# 2230_TubePitotDeporte_Schematic_v1_0_0.net
KiCad netlist of a schematic drawn in Altium Designer
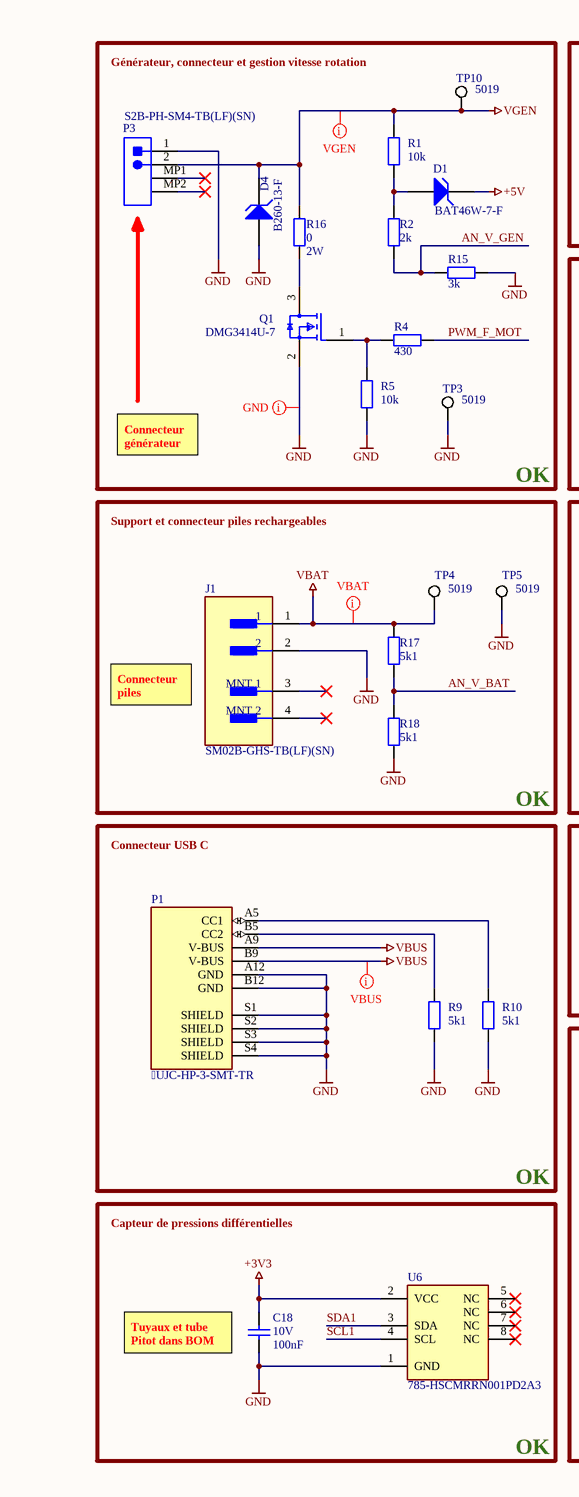
[diagram p0: 2230_TubePitotDeporte_Schematic_v1.0.0.SchDoc, left]
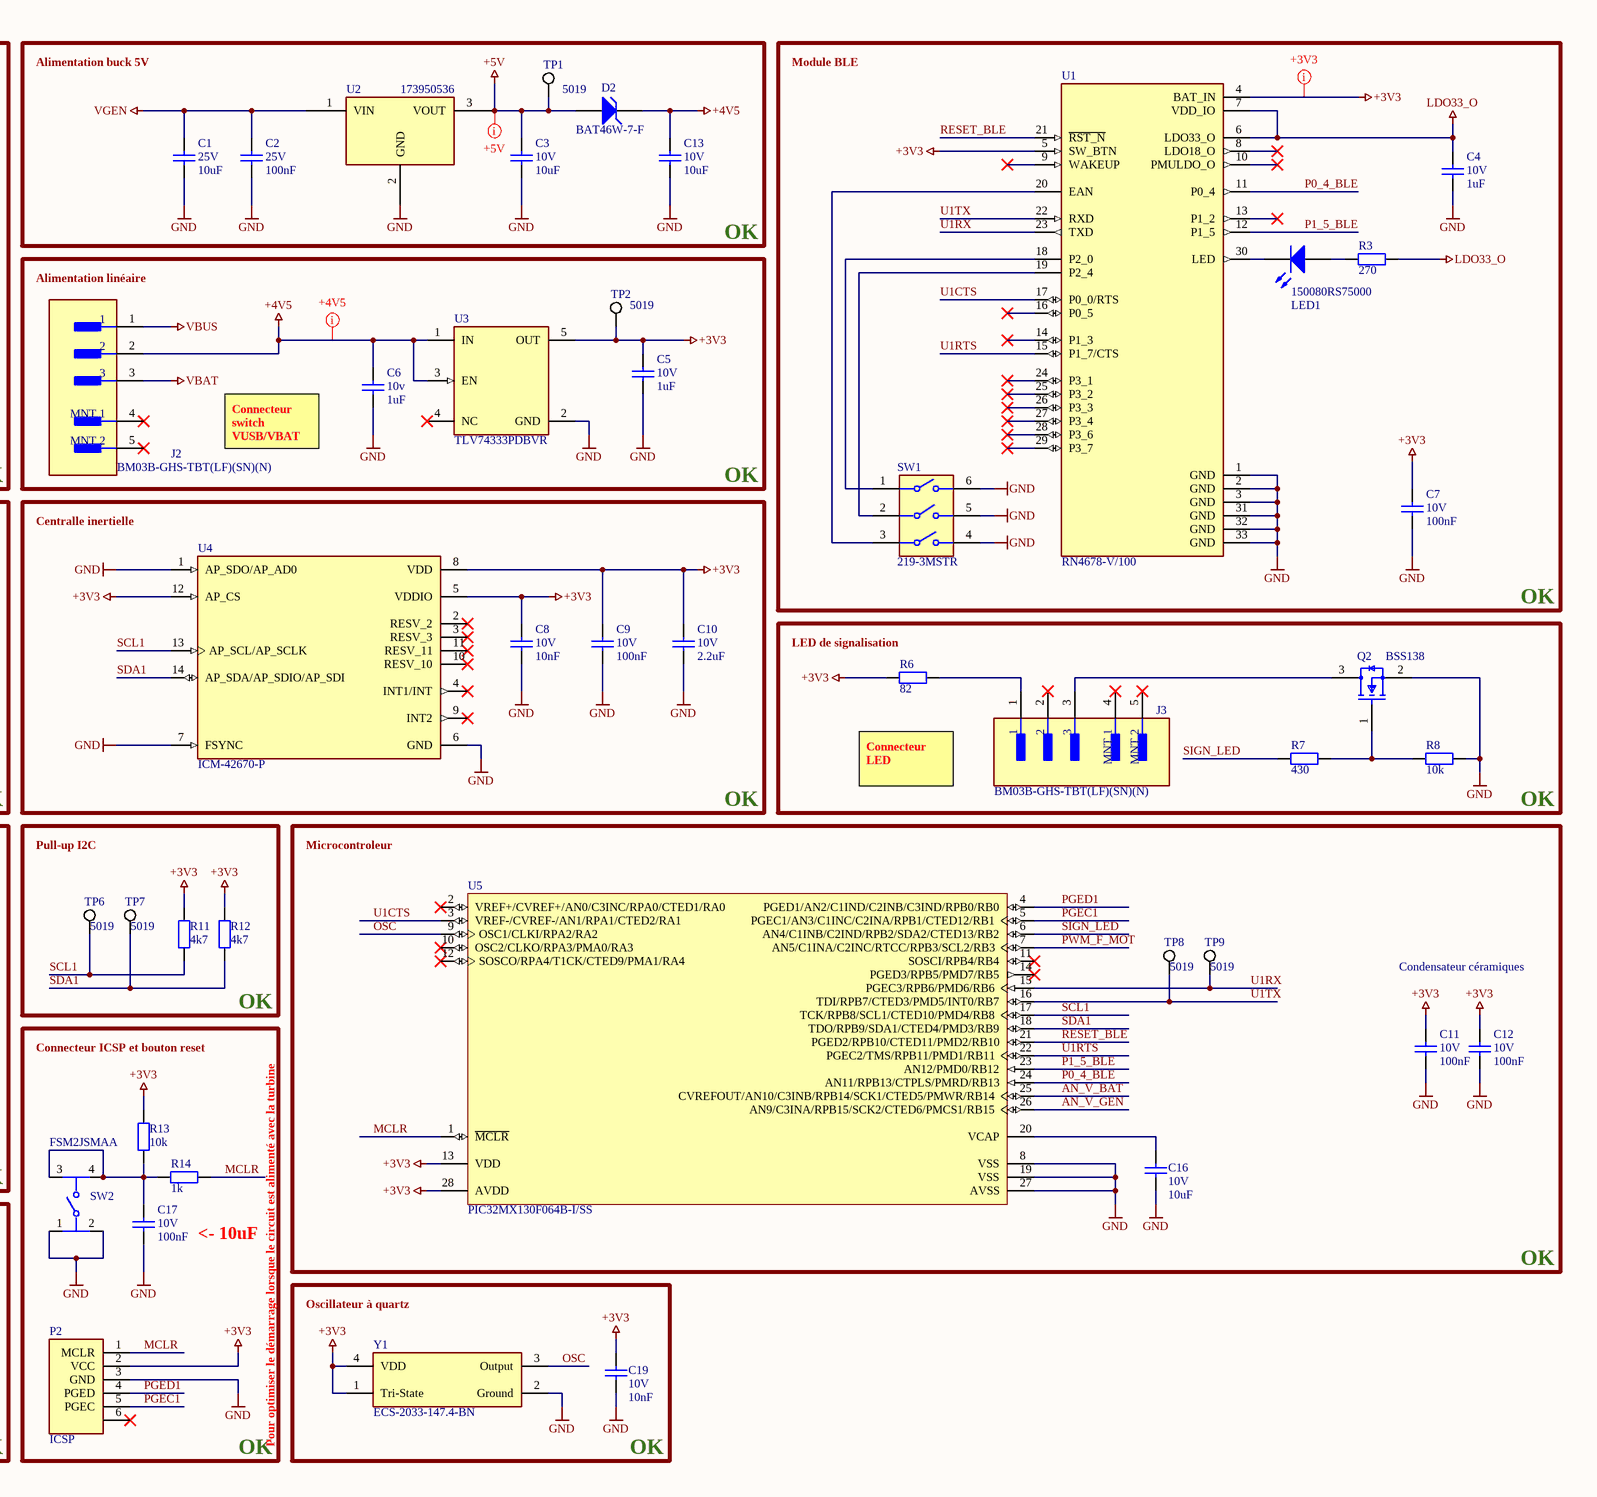
[diagram p1: 2230_TubePitotDeporte_Schematic_v1.0.0.SchDoc, right]

(export (version "E")
  (design (tool "Eeschema 10.0.6"))
  (components
    (comp (ref "C1")
      (value "25V")
      (footprint "0805 CAP T0.95")
      (description "Capacitor")
      (fields (field (name "ALTIUM_VALUE") "10uF") (field (name "PUBLISHER") "Altium Limited"))
      (libsource (lib "Miscellaneous Devices") (part "Cap"))
    )
    (comp (ref "C2")
      (value "25V")
      (footprint "0805 CAP T0.75")
      (description "Capacitor")
      (fields (field (name "ALTIUM_VALUE") "100nF") (field (name "PUBLISHER") "Altium Limited"))
      (libsource (lib "Miscellaneous Devices") (part "Cap"))
    )
    (comp (ref "C3")
      (value "10V")
      (footprint "0805 CAP T0.95")
      (description "Capacitor")
      (fields (field (name "ALTIUM_VALUE") "10uF") (field (name "PUBLISHER") "Altium Limited"))
      (libsource (lib "Miscellaneous Devices") (part "Cap"))
    )
    (comp (ref "C4")
      (value "10V")
      (footprint "0805 CAP T0.75")
      (description "Capacitor")
      (fields (field (name "ALTIUM_VALUE") "1uF") (field (name "PUBLISHER") "Altium Limited"))
      (libsource (lib "Miscellaneous Devices") (part "Cap"))
    )
    (comp (ref "C5")
      (value "10V")
      (footprint "0805 CAP T0.95")
      (description "Capacitor")
      (fields (field (name "ALTIUM_VALUE") "1uF") (field (name "PUBLISHER") "Altium Limited"))
      (libsource (lib "Miscellaneous Devices") (part "Cap"))
    )
    (comp (ref "C6")
      (value "10v")
      (footprint "0805 CAP T0.95")
      (description "Capacitor")
      (fields (field (name "ALTIUM_VALUE") "1uF") (field (name "PUBLISHER") "Altium Limited"))
      (libsource (lib "Miscellaneous Devices") (part "Cap"))
    )
    (comp (ref "C7")
      (value "10V")
      (footprint "0805 CAP T0.75")
      (description "Capacitor")
      (fields (field (name "ALTIUM_VALUE") "100nF") (field (name "PUBLISHER") "Altium Limited"))
      (libsource (lib "Miscellaneous Devices") (part "Cap"))
    )
    (comp (ref "C8")
      (value "10V")
      (footprint "0805 CAP T0.75")
      (description "Capacitor")
      (fields (field (name "ALTIUM_VALUE") "10nF") (field (name "PUBLISHER") "Altium Limited"))
      (libsource (lib "Miscellaneous Devices") (part "Cap"))
    )
    (comp (ref "C9")
      (value "10V")
      (footprint "0805 CAP T0.75")
      (description "Capacitor")
      (fields (field (name "ALTIUM_VALUE") "100nF") (field (name "PUBLISHER") "Altium Limited"))
      (libsource (lib "Miscellaneous Devices") (part "Cap"))
    )
    (comp (ref "C10")
      (value "10V")
      (footprint "0805 CAP T0.75")
      (description "Capacitor")
      (fields (field (name "ALTIUM_VALUE") "2.2uF") (field (name "PUBLISHER") "Altium Limited"))
      (libsource (lib "Miscellaneous Devices") (part "Cap"))
    )
    (comp (ref "C11")
      (value "10V")
      (footprint "0805 CAP T0.75")
      (description "Capacitor")
      (fields (field (name "ALTIUM_VALUE") "100nF") (field (name "PUBLISHER") "Altium Limited"))
      (libsource (lib "Miscellaneous Devices") (part "Cap"))
    )
    (comp (ref "C12")
      (value "10V")
      (footprint "0805 CAP T0.75")
      (description "Capacitor")
      (fields (field (name "ALTIUM_VALUE") "100nF") (field (name "PUBLISHER") "Altium Limited"))
      (libsource (lib "Miscellaneous Devices") (part "Cap"))
    )
    (comp (ref "C13")
      (value "10V")
      (footprint "0805 CAP T0.95")
      (description "Capacitor")
      (fields (field (name "ALTIUM_VALUE") "10uF") (field (name "PUBLISHER") "Altium Limited"))
      (libsource (lib "Miscellaneous Devices") (part "Cap"))
    )
    (comp (ref "C16")
      (value "10V")
      (footprint "0805 CAP T0.95")
      (description "Capacitor")
      (fields (field (name "ALTIUM_VALUE") "10uF") (field (name "PUBLISHER") "Altium Limited"))
      (libsource (lib "Miscellaneous Devices") (part "Cap"))
    )
    (comp (ref "C17")
      (value "10V")
      (footprint "0805 CAP T0.75")
      (description "Capacitor")
      (fields (field (name "ALTIUM_VALUE") "100nF") (field (name "PUBLISHER") "Altium Limited"))
      (libsource (lib "Miscellaneous Devices") (part "Cap"))
    )
    (comp (ref "C18")
      (value "10V")
      (footprint "0805 CAP T0.75")
      (description "Capacitor")
      (fields (field (name "ALTIUM_VALUE") "100nF") (field (name "PUBLISHER") "Altium Limited"))
      (libsource (lib "Miscellaneous Devices") (part "Cap"))
    )
    (comp (ref "C19")
      (value "10V")
      (footprint "0805 CAP T0.75")
      (description "Capacitor")
      (fields (field (name "ALTIUM_VALUE") "10nF") (field (name "PUBLISHER") "Altium Limited"))
      (libsource (lib "Miscellaneous Devices") (part "Cap"))
    )
    (comp (ref "D1")
      (value "BAT46W-7-F")
      (footprint "SOD123")
      (description "Zener Diode")
      (fields (field (name "PUBLISHER") "Altium Limited"))
      (libsource (lib "Miscellaneous Devices") (part "D Zener"))
    )
    (comp (ref "D2")
      (value "BAT46W-7-F")
      (footprint "SOD123")
      (description "Zener Diode")
      (fields (field (name "PUBLISHER") "Altium Limited"))
      (libsource (lib "Miscellaneous Devices") (part "D Zener"))
    )
    (comp (ref "D4")
      (value "B260-13-F")
      (footprint "SMB-2")
      (description "Zener Diode")
      (fields (field (name "PUBLISHER") "Altium Limited"))
      (libsource (lib "Miscellaneous Devices") (part "D Zener"))
    )
    (comp (ref "J1")
      (value "SM02B-GHS-TB(LF)(SN)")
      (footprint "FP-SM02B-GHS-TB_LF_SN-MFG")
      (description "CONN HEADER SMD R/A 2POS 1.25MM")
      (libsource (lib "Altium Content Vault") (part "56ec3178a87b3978bdc1b3682cd516a"))
    )
    (comp (ref "J2")
      (value "BM03B-GHS-TBT(LF)(SN)(N)")
      (footprint "FP-BM03B-GHS-TBT_LF_SN-MFG")
      (description "CONN HEADER SMD 3POS 1.25MM")
      (libsource (lib "") (part "38689d6f3df0f9b234c6ddcef280d85_1"))
    )
    (comp (ref "J3")
      (value "BM03B-GHS-TBT(LF)(SN)(N)")
      (footprint "FP-BM03B-GHS-TBT_LF_SN-MFG")
      (description "CONN HEADER SMD 3POS 1.25MM")
      (libsource (lib "Altium Content Vault") (part "38689d6f3df0f9b234c6ddcef280d85"))
    )
    (comp (ref "LED1")
      (value "150080RS75000")
      (footprint "0805_A")
      (description "SMD mono-color Chip LED, WL-SMCW, Red")
      (fields (field (name "MANUFACTURER") "Wuerth Elektronik"))
      (libsource (lib "Altium Content Vault") (part "WE-LED_K1A2-2"))
    )
    (comp (ref "P1")
      (value "UJC-HP-3-SMT-TR")
      (footprint "UJC-HP-3-SMT-TR")
      (description "USBC connector")
      (libsource (lib "2230_TubePitotDeporte_Library_v1.0.0") (part "UJC-HP-3-SMT-TR"))
    )
    (comp (ref "P2")
      (value "ICSP")
      (footprint "ICSP")
      (description "Prog")
      (libsource (lib "2230_TubePitotDeporte_Library_v1.0.0") (part "ICSP"))
    )
    (comp (ref "P3")
      (value "S2B-PH-SM4-TB(LF)(SN)")
      (footprint "JST- S2B-PH-SM4-TB(LF)(SN)-2_V")
      (description "Male Header, Pitch 2 mm, 1 x 2 Position, Height 5.5 mm, -25 to 85 degC, RoHS, Tape and Reel")
      (libsource (lib "Altium Content Vault") (part "CN-1P-2M-R2"))
    )
    (comp (ref "Q1")
      (value "DMG3414U-7")
      (footprint "FP-SOT23-IPC_B")
      (description "MOSFET N-CH 20V 4.2A SOT23")
      (libsource (lib "Altium Content Vault") (part "381a366367e4312d0f7d2747150cb42"))
    )
    (comp (ref "Q2")
      (value "BSS138")
      (footprint "FP-318-08-IPC_A")
      (description "MOSFET N-CH 50V 220MA SOT-23")
      (libsource (lib "Altium Content Vault") (part "3b9c635fedb024a5347a57b145af9cc"))
    )
    (comp (ref "R1")
      (value "10k")
      (footprint "0805 Res")
      (description "Resistor")
      (fields (field (name "PUBLISHER") "Altium Limited"))
      (libsource (lib "") (part "Res2_1"))
    )
    (comp (ref "R2")
      (value "2k")
      (footprint "0805 Res")
      (description "Resistor")
      (fields (field (name "PUBLISHER") "Altium Limited"))
      (libsource (lib "Miscellaneous Devices") (part "Res2"))
    )
    (comp (ref "R3")
      (value "270")
      (footprint "0805 Res")
      (description "Resistor")
      (fields (field (name "Comment") "270R") (field (name "PUBLISHER") "Altium Limited"))
      (libsource (lib "") (part "Res2_2"))
    )
    (comp (ref "R4")
      (value "430")
      (footprint "0805 Res")
      (description "Resistor")
      (fields (field (name "Comment") "430R") (field (name "PUBLISHER") "Altium Limited"))
      (libsource (lib "") (part "Res2_2"))
    )
    (comp (ref "R5")
      (value "10k")
      (footprint "0805 Res")
      (description "Resistor")
      (fields (field (name "PUBLISHER") "Altium Limited"))
      (libsource (lib "") (part "Res2_1"))
    )
    (comp (ref "R6")
      (value "82")
      (footprint "0805 Res")
      (description "Resistor")
      (fields (field (name "Comment") "82R") (field (name "PUBLISHER") "Altium Limited"))
      (libsource (lib "") (part "Res2_3"))
    )
    (comp (ref "R7")
      (value "430")
      (footprint "0805 Res")
      (description "Resistor")
      (fields (field (name "Comment") "430R") (field (name "PUBLISHER") "Altium Limited"))
      (libsource (lib "") (part "Res2_3"))
    )
    (comp (ref "R8")
      (value "10k")
      (footprint "0805 Res")
      (description "Resistor")
      (fields (field (name "PUBLISHER") "Altium Limited"))
      (libsource (lib "") (part "Res2_3"))
    )
    (comp (ref "R9")
      (value "5k1")
      (footprint "0805 Res")
      (description "Resistor")
      (fields (field (name "PUBLISHER") "Altium Limited"))
      (libsource (lib "") (part "Res2_1"))
    )
    (comp (ref "R10")
      (value "5k1")
      (footprint "0805 Res")
      (description "Resistor")
      (fields (field (name "PUBLISHER") "Altium Limited"))
      (libsource (lib "") (part "Res2_1"))
    )
    (comp (ref "R11")
      (value "4k7")
      (footprint "0805 Res")
      (description "Resistor")
      (fields (field (name "Comment") "10k") (field (name "PUBLISHER") "Altium Limited"))
      (libsource (lib "Miscellaneous Devices") (part "Res2"))
    )
    (comp (ref "R12")
      (value "4k7")
      (footprint "0805 Res")
      (description "Resistor")
      (fields (field (name "Comment") "10k") (field (name "PUBLISHER") "Altium Limited"))
      (libsource (lib "Miscellaneous Devices") (part "Res2"))
    )
    (comp (ref "R13")
      (value "10k")
      (footprint "0805 Res")
      (description "Resistor")
      (fields (field (name "PUBLISHER") "Altium Limited"))
      (libsource (lib "Miscellaneous Devices") (part "Res2"))
    )
    (comp (ref "R14")
      (value "1k")
      (footprint "0805 Res")
      (description "Resistor")
      (fields (field (name "PUBLISHER") "Altium Limited"))
      (libsource (lib "") (part "Res2_2"))
    )
    (comp (ref "R15")
      (value "3k")
      (footprint "0805 Res")
      (description "Resistor")
      (fields (field (name "PUBLISHER") "Altium Limited"))
      (libsource (lib "") (part "Res2_2"))
    )
    (comp (ref "R16")
      (value "0")
      (footprint "RES 2W")
      (description "Resistor")
      (fields
        (field (name "POWER") "2W")
        (field (name "Comment") "0R")
        (field (name "PUBLISHER") "Altium Limited")
      )
      (libsource (lib "") (part "Res2_1"))
    )
    (comp (ref "R17")
      (value "5k1")
      (footprint "0805 Res")
      (description "Resistor")
      (fields (field (name "PUBLISHER") "Altium Limited"))
      (libsource (lib "Miscellaneous Devices") (part "Res2"))
    )
    (comp (ref "R18")
      (value "5k1")
      (footprint "0805 Res")
      (description "Resistor")
      (fields (field (name "PUBLISHER") "Altium Limited"))
      (libsource (lib "Miscellaneous Devices") (part "Res2"))
    )
    (comp (ref "SW1")
      (value "219-3MSTR")
      (footprint "FP-219-3MSTR-MFG")
      (description "SWITCH SLIDE DIP SPST 100MA 20V")
      (libsource (lib "Altium Content Vault") (part "7c490946f25aa2bb1cd4cef5bc3ec4e"))
    )
    (comp (ref "SW2")
      (value "FSM2JSMAA")
      (footprint "FP-FSM2JSMAA-MFG")
      (description "SWITCH TACTILE SPST-NO 0.05A 24V")
      (fields
        (field (name "MANUFACTURER") "TE Connectivity")
        (field (name "OCTOPART") "https://octopart.com/fsm2jsmaa-te+connectivity-41720620")
      )
      (libsource (lib "Altium Content Vault") (part "b8895f3f4cefb76e1819d2863dba89b"))
    )
    (comp (ref "TP1")
      (value "5019")
      (footprint "KSTN-5019_V")
      (description "Test Point, 1 Position SMD, RoHS, Tape and Reel")
      (libsource (lib "Altium Content Vault") (part "TESTPOINT_WHITE"))
    )
    (comp (ref "TP2")
      (value "5019")
      (footprint "KSTN-5019_V")
      (description "Test Point, 1 Position SMD, RoHS, Tape and Reel")
      (libsource (lib "Altium Content Vault") (part "TESTPOINT_WHITE"))
    )
    (comp (ref "TP3")
      (value "5019")
      (footprint "KSTN-5019_V")
      (description "Test Point, 1 Position SMD, RoHS, Tape and Reel")
      (libsource (lib "Altium Content Vault") (part "TESTPOINT_WHITE"))
    )
    (comp (ref "TP4")
      (value "5019")
      (footprint "KSTN-5019_V")
      (description "Test Point, 1 Position SMD, RoHS, Tape and Reel")
      (libsource (lib "Altium Content Vault") (part "TESTPOINT_WHITE"))
    )
    (comp (ref "TP5")
      (value "5019")
      (footprint "KSTN-5019_V")
      (description "Test Point, 1 Position SMD, RoHS, Tape and Reel")
      (libsource (lib "Altium Content Vault") (part "TESTPOINT_WHITE"))
    )
    (comp (ref "TP6")
      (value "5019")
      (footprint "KSTN-5019_V")
      (description "Test Point, 1 Position SMD, RoHS, Tape and Reel")
      (libsource (lib "Altium Content Vault") (part "TESTPOINT_WHITE"))
    )
    (comp (ref "TP7")
      (value "5019")
      (footprint "KSTN-5019_V")
      (description "Test Point, 1 Position SMD, RoHS, Tape and Reel")
      (libsource (lib "Altium Content Vault") (part "TESTPOINT_WHITE"))
    )
    (comp (ref "TP8")
      (value "5019")
      (footprint "KSTN-5019_V")
      (description "Test Point, 1 Position SMD, RoHS, Tape and Reel")
      (libsource (lib "Altium Content Vault") (part "TESTPOINT_WHITE"))
    )
    (comp (ref "TP9")
      (value "5019")
      (footprint "KSTN-5019_V")
      (description "Test Point, 1 Position SMD, RoHS, Tape and Reel")
      (libsource (lib "Altium Content Vault") (part "TESTPOINT_WHITE"))
    )
    (comp (ref "TP10")
      (value "5019")
      (footprint "KSTN-5019_V")
      (description "Test Point, 1 Position SMD, RoHS, Tape and Reel")
      (libsource (lib "Altium Content Vault") (part "TESTPOINT_WHITE"))
    )
    (comp (ref "U1")
      (value "RN4678-V/100")
      (footprint "RN4678-V_RM100")
      (description "Bluetooth Bluetooth v5.0 Transceiver Module 2.4GHz Integrated, Chip Surface Mount")
      (libsource (lib "2230_TubePitotDeporte_Library_v1.0.0") (part "RN4678-V/100"))
    )
    (comp (ref "U2")
      (value "173950536")
      (footprint "173950536")
      (description "Buck 5V")
      (libsource (lib "2230_TubePitotDeporte_Library_v1.0.0") (part "710-173950536"))
    )
    (comp (ref "U3")
      (value "TLV74333PDBVR")
      (footprint "FP-DBV0005A-MFG")
      (description "IC REG LINEAR 3.3V 300MA SOT23-5")
      (fields
        (field (name "OCTOPART") "https://octopart.com/tlv74333pdbvr-texas+instruments-84791760")
        (field (name "MANUFACTURER") "Texas Instruments")
      )
      (libsource (lib "Altium Content Vault") (part "3a8dd6e68b3b0d4ea301bae8a2f3989"))
    )
    (comp (ref "U4")
      (value "ICM-42670-P")
      (footprint "ICM-42670-P")
      (description "6 axis IMU")
      (libsource (lib "2230_TubePitotDeporte_Library_v1.0.0") (part "ICM-42670-P"))
    )
    (comp (ref "U5")
      (value "PIC32MX130F064B-I/SS")
      (footprint "PIC32MX130F064B-I/SS")
      (libsource (lib "2230_TubePitotDeporte_Library_v1.0.0") (part "PIC32MX130F064B-I/SS"))
    )
    (comp (ref "U6")
      (value "785-HSCMRRN001PD2A3")
      (footprint "HSCMRRN001PD2A3")
      (description "Air sensor")
      (libsource (lib "2230_TubePitotDeporte_Library_v1.0.0") (part "785-HSCMRRN001PD2A3"))
    )
    (comp (ref "Y1")
      (value "ECS-2033-147.4-BN")
      (footprint "ECS-2033-147.4-BN")
      (description "ECS-2033-147.4-BN 14.7456 MHz Oscillator")
      (libsource (lib "2230_TubePitotDeporte_Library_v1.0.0") (part "ECS-2033-147.4-BN"))
    )
  )
  (nets
    (net (code "1") (name "+3V3") (class "Default")
      (node (ref "C10") (pin "2") (pinfunction "2_2") (pintype "passive"))
      (node (ref "C11") (pin "2") (pinfunction "2_2") (pintype "passive"))
      (node (ref "C12") (pin "2") (pinfunction "2_2") (pintype "passive"))
      (node (ref "C18") (pin "2") (pinfunction "2_2") (pintype "passive"))
      (node (ref "C19") (pin "1") (pinfunction "1_1") (pintype "passive"))
      (node (ref "C5") (pin "2") (pinfunction "2_2") (pintype "passive"))
      (node (ref "C7") (pin "2") (pinfunction "2_2") (pintype "passive"))
      (node (ref "C8") (pin "2") (pinfunction "2_2") (pintype "passive"))
      (node (ref "C9") (pin "2") (pinfunction "2_2") (pintype "passive"))
      (node (ref "P2") (pin "2") (pinfunction "VCC_2") (pintype "passive"))
      (node (ref "R11") (pin "1") (pinfunction "1_1") (pintype "passive"))
      (node (ref "R12") (pin "1") (pinfunction "1_1") (pintype "passive"))
      (node (ref "R13") (pin "1") (pinfunction "1_1") (pintype "passive"))
      (node (ref "R6") (pin "1") (pinfunction "1_1") (pintype "passive"))
      (node (ref "TP2") (pin "1") (pinfunction "1_1") (pintype "passive"))
      (node (ref "U1") (pin "4") (pinfunction "BAT_IN_4") (pintype "power_in"))
      (node (ref "U1") (pin "5") (pinfunction "SW_BTN_5") (pintype "input"))
      (node (ref "U3") (pin "5") (pinfunction "OUT_5") (pintype "power_in"))
      (node (ref "U4") (pin "12") (pinfunction "AP_CS_12") (pintype "input"))
      (node (ref "U4") (pin "5") (pinfunction "VDDIO_5") (pintype "power_in"))
      (node (ref "U4") (pin "8") (pinfunction "VDD_8") (pintype "power_in"))
      (node (ref "U5") (pin "13") (pinfunction "VDD_13") (pintype "power_in"))
      (node (ref "U5") (pin "28") (pinfunction "AVDD_28") (pintype "power_in"))
      (node (ref "U6") (pin "2") (pinfunction "VCC_2") (pintype "passive"))
      (node (ref "Y1") (pin "1") (pinfunction "Tri-State_1") (pintype "passive"))
      (node (ref "Y1") (pin "4") (pinfunction "VDD_4") (pintype "power_in"))
    )
    (net (code "2") (name "+4V5") (class "Default")
      (node (ref "C13") (pin "2") (pinfunction "2_2") (pintype "passive"))
      (node (ref "C6") (pin "2") (pinfunction "2_2") (pintype "passive"))
      (node (ref "D2") (pin "2") (pinfunction "K_2") (pintype "passive"))
      (node (ref "J2") (pin "2") (pinfunction "2_2") (pintype "passive"))
      (node (ref "U3") (pin "1") (pinfunction "IN_1") (pintype "power_in"))
      (node (ref "U3") (pin "3") (pinfunction "EN_3") (pintype "input"))
    )
    (net (code "3") (name "+5V") (class "Default")
      (node (ref "C3") (pin "2") (pinfunction "2_2") (pintype "passive"))
      (node (ref "D1") (pin "2") (pinfunction "K_2") (pintype "passive"))
      (node (ref "D2") (pin "1") (pinfunction "A_1") (pintype "passive"))
      (node (ref "TP1") (pin "1") (pinfunction "1_1") (pintype "passive"))
      (node (ref "U2") (pin "3") (pinfunction "VOUT_3") (pintype "passive"))
    )
    (net (code "4") (name "/AN_V_BAT") (class "Default")
      (node (ref "R17") (pin "2") (pinfunction "2_2") (pintype "passive"))
      (node (ref "R18") (pin "1") (pinfunction "1_1") (pintype "passive"))
      (node (ref "U5") (pin "25") (pinfunction "CVREFOUT/AN10/C3INB/RPB14/SCK1/CTED5/PMWR/RB14_25") (pintype "bidirectional"))
    )
    (net (code "5") (name "/AN_V_GEN") (class "Default")
      (node (ref "R15") (pin "2") (pinfunction "2_2") (pintype "passive"))
      (node (ref "R2") (pin "2") (pinfunction "2_2") (pintype "passive"))
      (node (ref "U5") (pin "26") (pinfunction "AN9/C3INA/RPB15/SCK2/CTED6/PMCS1/RB15_26") (pintype "bidirectional"))
    )
    (net (code "6") (name "/MCLR") (class "Default")
      (node (ref "P2") (pin "1") (pinfunction "MCLR_1") (pintype "passive"))
      (node (ref "R14") (pin "1") (pinfunction "1_1") (pintype "passive"))
      (node (ref "U5") (pin "1") (pinfunction "~{MCLR}_1") (pintype "bidirectional"))
    )
    (net (code "7") (name "/OSC") (class "Default")
      (node (ref "U5") (pin "9") (pinfunction "OSC1/CLKI/RPA2/RA2_9") (pintype "bidirectional"))
      (node (ref "Y1") (pin "3") (pinfunction "Output_3") (pintype "passive"))
    )
    (net (code "8") (name "/P0_4_BLE") (class "Default")
      (node (ref "U1") (pin "11") (pinfunction "P0_4_11") (pintype "output"))
      (node (ref "U5") (pin "24") (pinfunction "AN11/RPB13/CTPLS/PMRD/RB13_24") (pintype "input"))
    )
    (net (code "9") (name "/P1_5_BLE") (class "Default")
      (node (ref "U1") (pin "12") (pinfunction "P1_5_12") (pintype "output"))
      (node (ref "U5") (pin "23") (pinfunction "AN12/PMD0/RB12_23") (pintype "input"))
    )
    (net (code "10") (name "/PGEC1") (class "Default")
      (node (ref "P2") (pin "5") (pinfunction "PGEC_5") (pintype "passive"))
      (node (ref "U5") (pin "5") (pinfunction "PGEC1/AN3/C1INC/C2INA/RPB1/CTED12/RB1_5") (pintype "bidirectional"))
    )
    (net (code "11") (name "/PGED1") (class "Default")
      (node (ref "P2") (pin "4") (pinfunction "PGED_4") (pintype "passive"))
      (node (ref "U5") (pin "4") (pinfunction "PGED1/AN2/C1IND/C2INB/C3IND/RPB0/RB0_4") (pintype "bidirectional"))
    )
    (net (code "12") (name "/PWM_F_MOT") (class "Default")
      (node (ref "R4") (pin "1") (pinfunction "1_1") (pintype "passive"))
      (node (ref "U5") (pin "7") (pinfunction "AN5/C1INA/C2INC/RTCC/RPB3/SCL2/RB3_7") (pintype "bidirectional"))
    )
    (net (code "13") (name "/RESET_BLE") (class "Default")
      (node (ref "U1") (pin "21") (pinfunction "~{RST_N}_21") (pintype "input"))
      (node (ref "U5") (pin "21") (pinfunction "PGED2/RPB10/CTED11/PMD2/RB10_21") (pintype "bidirectional"))
    )
    (net (code "14") (name "/SCL1") (class "Default")
      (node (ref "R11") (pin "2") (pinfunction "2_2") (pintype "passive"))
      (node (ref "TP6") (pin "1") (pinfunction "1_1") (pintype "passive"))
      (node (ref "U4") (pin "13") (pinfunction "AP_SCL/AP_SCLK_13") (pintype "input"))
      (node (ref "U5") (pin "17") (pinfunction "TCK/RPB8/SCL1/CTED10/PMD4/RB8_17") (pintype "bidirectional"))
      (node (ref "U6") (pin "4") (pinfunction "SCL_4") (pintype "passive"))
    )
    (net (code "15") (name "/SDA1") (class "Default")
      (node (ref "R12") (pin "2") (pinfunction "2_2") (pintype "passive"))
      (node (ref "TP7") (pin "1") (pinfunction "1_1") (pintype "passive"))
      (node (ref "U4") (pin "14") (pinfunction "AP_SDA/AP_SDIO/AP_SDI_14") (pintype "bidirectional"))
      (node (ref "U5") (pin "18") (pinfunction "TDO/RPB9/SDA1/CTED4/PMD3/RB9_18") (pintype "bidirectional"))
      (node (ref "U6") (pin "3") (pinfunction "SDA_3") (pintype "passive"))
    )
    (net (code "16") (name "/SIGN_LED") (class "Default")
      (node (ref "R7") (pin "1") (pinfunction "1_1") (pintype "passive"))
      (node (ref "U5") (pin "6") (pinfunction "AN4/C1INB/C2IND/RPB2/SDA2/CTED13/RB2_6") (pintype "bidirectional"))
    )
    (net (code "17") (name "/U1CTS") (class "Default")
      (node (ref "U1") (pin "17") (pinfunction "P0_0/RTS_17") (pintype "bidirectional"))
      (node (ref "U5") (pin "3") (pinfunction "VREF-/CVREF-/AN1/RPA1/CTED2/RA1_3") (pintype "bidirectional"))
    )
    (net (code "18") (name "/U1RTS") (class "Default")
      (node (ref "U1") (pin "15") (pinfunction "P1_7/CTS_15") (pintype "bidirectional"))
      (node (ref "U5") (pin "22") (pinfunction "PGEC2/TMS/RPB11/PMD1/RB11_22") (pintype "bidirectional"))
    )
    (net (code "19") (name "/U1RX") (class "Default")
      (node (ref "TP9") (pin "1") (pinfunction "1_1") (pintype "passive"))
      (node (ref "U1") (pin "23") (pinfunction "TXD_23") (pintype "output"))
      (node (ref "U5") (pin "15") (pinfunction "PGEC3/RPB6/PMD6/RB6_15") (pintype "input"))
    )
    (net (code "20") (name "/U1TX") (class "Default")
      (node (ref "TP8") (pin "1") (pinfunction "1_1") (pintype "passive"))
      (node (ref "U1") (pin "22") (pinfunction "RXD_22") (pintype "input"))
      (node (ref "U5") (pin "16") (pinfunction "TDI/RPB7/CTED3/PMD5/INT0/RB7_16") (pintype "bidirectional"))
    )
    (net (code "21") (name "GND") (class "Default")
      (node (ref "C1") (pin "1") (pinfunction "1_1") (pintype "passive"))
      (node (ref "C10") (pin "1") (pinfunction "1_1") (pintype "passive"))
      (node (ref "C11") (pin "1") (pinfunction "1_1") (pintype "passive"))
      (node (ref "C12") (pin "1") (pinfunction "1_1") (pintype "passive"))
      (node (ref "C13") (pin "1") (pinfunction "1_1") (pintype "passive"))
      (node (ref "C16") (pin "1") (pinfunction "1_1") (pintype "passive"))
      (node (ref "C17") (pin "1") (pinfunction "1_1") (pintype "passive"))
      (node (ref "C18") (pin "1") (pinfunction "1_1") (pintype "passive"))
      (node (ref "C19") (pin "2") (pinfunction "2_2") (pintype "passive"))
      (node (ref "C2") (pin "1") (pinfunction "1_1") (pintype "passive"))
      (node (ref "C3") (pin "1") (pinfunction "1_1") (pintype "passive"))
      (node (ref "C4") (pin "1") (pinfunction "1_1") (pintype "passive"))
      (node (ref "C5") (pin "1") (pinfunction "1_1") (pintype "passive"))
      (node (ref "C6") (pin "1") (pinfunction "1_1") (pintype "passive"))
      (node (ref "C7") (pin "1") (pinfunction "1_1") (pintype "passive"))
      (node (ref "C8") (pin "1") (pinfunction "1_1") (pintype "passive"))
      (node (ref "C9") (pin "1") (pinfunction "1_1") (pintype "passive"))
      (node (ref "D4") (pin "1") (pinfunction "A_1") (pintype "passive"))
      (node (ref "J1") (pin "2") (pinfunction "2_2") (pintype "passive"))
      (node (ref "P1") (pin "A12") (pinfunction "GND_A12") (pintype "power_in"))
      (node (ref "P1") (pin "B12") (pinfunction "GND_B12") (pintype "power_in"))
      (node (ref "P1") (pin "S1") (pinfunction "SHIELD_S1") (pintype "passive"))
      (node (ref "P1") (pin "S2") (pinfunction "SHIELD_S2") (pintype "passive"))
      (node (ref "P1") (pin "S3") (pinfunction "SHIELD_S3") (pintype "passive"))
      (node (ref "P1") (pin "S4") (pinfunction "SHIELD_S4") (pintype "passive"))
      (node (ref "P2") (pin "3") (pinfunction "GND_3") (pintype "passive"))
      (node (ref "P3") (pin "1") (pinfunction "1_1") (pintype "passive"))
      (node (ref "Q1") (pin "2") (pinfunction "S_2") (pintype "passive"))
      (node (ref "Q2") (pin "2") (pinfunction "S_2") (pintype "passive"))
      (node (ref "R10") (pin "1") (pinfunction "1_1") (pintype "passive"))
      (node (ref "R15") (pin "1") (pinfunction "1_1") (pintype "passive"))
      (node (ref "R18") (pin "2") (pinfunction "2_2") (pintype "passive"))
      (node (ref "R5") (pin "1") (pinfunction "1_1") (pintype "passive"))
      (node (ref "R8") (pin "2") (pinfunction "2_2") (pintype "passive"))
      (node (ref "R9") (pin "1") (pinfunction "1_1") (pintype "passive"))
      (node (ref "SW1") (pin "4") (pinfunction "4_4") (pintype "passive"))
      (node (ref "SW1") (pin "5") (pinfunction "5_5") (pintype "passive"))
      (node (ref "SW1") (pin "6") (pinfunction "6_6") (pintype "passive"))
      (node (ref "SW2") (pin "1") (pinfunction "1_1") (pintype "passive"))
      (node (ref "SW2") (pin "2") (pinfunction "2_2") (pintype "passive"))
      (node (ref "TP3") (pin "1") (pinfunction "1_1") (pintype "passive"))
      (node (ref "TP5") (pin "1") (pinfunction "1_1") (pintype "passive"))
      (node (ref "U1") (pin "1") (pinfunction "GND_1") (pintype "power_in"))
      (node (ref "U1") (pin "2") (pinfunction "GND_2") (pintype "power_in"))
      (node (ref "U1") (pin "3") (pinfunction "GND_3") (pintype "power_in"))
      (node (ref "U1") (pin "31") (pinfunction "GND_31") (pintype "power_in"))
      (node (ref "U1") (pin "32") (pinfunction "GND_32") (pintype "power_in"))
      (node (ref "U1") (pin "33") (pinfunction "GND_33") (pintype "power_in"))
      (node (ref "U2") (pin "2") (pinfunction "GND_2") (pintype "passive"))
      (node (ref "U3") (pin "2") (pinfunction "GND_2") (pintype "power_in"))
      (node (ref "U4") (pin "1") (pinfunction "AP_SDO/AP_AD0_1") (pintype "input"))
      (node (ref "U4") (pin "6") (pinfunction "GND_6") (pintype "power_in"))
      (node (ref "U4") (pin "7") (pinfunction "FSYNC_7") (pintype "input"))
      (node (ref "U5") (pin "19") (pinfunction "VSS_19") (pintype "power_in"))
      (node (ref "U5") (pin "27") (pinfunction "AVSS_27") (pintype "power_in"))
      (node (ref "U5") (pin "8") (pinfunction "VSS_8") (pintype "power_in"))
      (node (ref "U6") (pin "1") (pinfunction "GND_1") (pintype "passive"))
      (node (ref "Y1") (pin "2") (pinfunction "Ground_2") (pintype "power_in"))
    )
    (net (code "22") (name "LDO33_O") (class "Default")
      (node (ref "C4") (pin "2") (pinfunction "2_2") (pintype "passive"))
      (node (ref "R3") (pin "1") (pinfunction "1_1") (pintype "passive"))
      (node (ref "U1") (pin "6") (pinfunction "LDO33_O_6") (pintype "power_in"))
      (node (ref "U1") (pin "7") (pinfunction "VDD_IO_7") (pintype "power_in"))
    )
    (net (code "23") (name "Net-(C17-Pad2)") (class "Default")
      (node (ref "C17") (pin "2") (pinfunction "2_2") (pintype "passive"))
      (node (ref "R13") (pin "2") (pinfunction "2_2") (pintype "passive"))
      (node (ref "R14") (pin "2") (pinfunction "2_2") (pintype "passive"))
      (node (ref "SW2") (pin "3") (pinfunction "3_3") (pintype "passive"))
      (node (ref "SW2") (pin "4") (pinfunction "4_4") (pintype "passive"))
    )
    (net (code "24") (name "Net-(D1-A)") (class "Default")
      (node (ref "D1") (pin "1") (pinfunction "A_1") (pintype "passive"))
      (node (ref "R1") (pin "1") (pinfunction "1_1") (pintype "passive"))
      (node (ref "R2") (pin "1") (pinfunction "1_1") (pintype "passive"))
    )
    (net (code "25") (name "Net-(J3-Pad1)") (class "Default")
      (node (ref "J3") (pin "1") (pinfunction "1_1") (pintype "passive"))
      (node (ref "R6") (pin "2") (pinfunction "2_2") (pintype "passive"))
    )
    (net (code "26") (name "Net-(LED1-A)") (class "Default")
      (node (ref "LED1") (pin "2") (pinfunction "A_2") (pintype "passive"))
      (node (ref "R3") (pin "2") (pinfunction "2_2") (pintype "passive"))
    )
    (net (code "27") (name "Net-(LED1-K)") (class "Default")
      (node (ref "LED1") (pin "1") (pinfunction "K_1") (pintype "passive"))
      (node (ref "U1") (pin "30") (pinfunction "LED_30") (pintype "output"))
    )
    (net (code "28") (name "Net-(P1-CC1)") (class "Default")
      (node (ref "P1") (pin "A5") (pinfunction "CC1_A5") (pintype "bidirectional"))
      (node (ref "R10") (pin "2") (pinfunction "2_2") (pintype "passive"))
    )
    (net (code "29") (name "Net-(P1-CC2)") (class "Default")
      (node (ref "P1") (pin "B5") (pinfunction "CC2_B5") (pintype "bidirectional"))
      (node (ref "R9") (pin "2") (pinfunction "2_2") (pintype "passive"))
    )
    (net (code "30") (name "Net-(Q1-D)") (class "Default")
      (node (ref "Q1") (pin "3") (pinfunction "D_3") (pintype "passive"))
      (node (ref "R16") (pin "1") (pinfunction "1_1") (pintype "passive"))
    )
    (net (code "31") (name "Net-(Q1-G)") (class "Default")
      (node (ref "Q1") (pin "1") (pinfunction "G_1") (pintype "passive"))
      (node (ref "R4") (pin "2") (pinfunction "2_2") (pintype "passive"))
      (node (ref "R5") (pin "2") (pinfunction "2_2") (pintype "passive"))
    )
    (net (code "32") (name "Net-(Q2-D)") (class "Default")
      (node (ref "J3") (pin "3") (pinfunction "3_3") (pintype "passive"))
      (node (ref "Q2") (pin "3") (pinfunction "D_3") (pintype "passive"))
    )
    (net (code "33") (name "Net-(Q2-G)") (class "Default")
      (node (ref "Q2") (pin "1") (pinfunction "G_1") (pintype "passive"))
      (node (ref "R7") (pin "2") (pinfunction "2_2") (pintype "passive"))
      (node (ref "R8") (pin "1") (pinfunction "1_1") (pintype "passive"))
    )
    (net (code "34") (name "Net-(U1-EAN)") (class "Default")
      (node (ref "SW1") (pin "3") (pinfunction "3_3") (pintype "passive"))
      (node (ref "U1") (pin "20") (pinfunction "EAN_20") (pintype "passive"))
    )
    (net (code "35") (name "Net-(U1-P2_0)") (class "Default")
      (node (ref "SW1") (pin "1") (pinfunction "1_1") (pintype "passive"))
      (node (ref "U1") (pin "18") (pinfunction "P2_0_18") (pintype "passive"))
    )
    (net (code "36") (name "Net-(U1-P2_4)") (class "Default")
      (node (ref "SW1") (pin "2") (pinfunction "2_2") (pintype "passive"))
      (node (ref "U1") (pin "19") (pinfunction "P2_4_19") (pintype "passive"))
    )
    (net (code "37") (name "Net-(U5-VCAP)") (class "Default")
      (node (ref "C16") (pin "2") (pinfunction "2_2") (pintype "passive"))
      (node (ref "U5") (pin "20") (pinfunction "VCAP_20") (pintype "passive"))
    )
    (net (code "38") (name "VBAT") (class "Default")
      (node (ref "J1") (pin "1") (pinfunction "1_1") (pintype "passive"))
      (node (ref "J2") (pin "3") (pinfunction "3_3") (pintype "passive"))
      (node (ref "R17") (pin "1") (pinfunction "1_1") (pintype "passive"))
      (node (ref "TP4") (pin "1") (pinfunction "1_1") (pintype "passive"))
    )
    (net (code "39") (name "VBUS") (class "Default")
      (node (ref "J2") (pin "1") (pinfunction "1_1") (pintype "passive"))
      (node (ref "P1") (pin "A9") (pinfunction "V-BUS_A9") (pintype "power_in"))
      (node (ref "P1") (pin "B9") (pinfunction "V-BUS_B9") (pintype "power_in"))
    )
    (net (code "40") (name "VGEN") (class "Default")
      (node (ref "C1") (pin "2") (pinfunction "2_2") (pintype "passive"))
      (node (ref "C2") (pin "2") (pinfunction "2_2") (pintype "passive"))
      (node (ref "D4") (pin "2") (pinfunction "K_2") (pintype "passive"))
      (node (ref "P3") (pin "2") (pinfunction "2_2") (pintype "passive"))
      (node (ref "R1") (pin "2") (pinfunction "2_2") (pintype "passive"))
      (node (ref "R16") (pin "2") (pinfunction "2_2") (pintype "passive"))
      (node (ref "TP10") (pin "1") (pinfunction "1_1") (pintype "passive"))
      (node (ref "U2") (pin "1") (pinfunction "VIN_1") (pintype "passive"))
    )
    (net (code "41") (name "unconnected-(J1-MNT_1-Pad3)") (class "Default")
      (node (ref "J1") (pin "3") (pinfunction "MNT_1_3") (pintype "passive+no_connect"))
    )
    (net (code "42") (name "unconnected-(J1-MNT_2-Pad4)") (class "Default")
      (node (ref "J1") (pin "4") (pinfunction "MNT_2_4") (pintype "passive+no_connect"))
    )
    (net (code "43") (name "unconnected-(J2-MNT_1-Pad4)") (class "Default")
      (node (ref "J2") (pin "4") (pinfunction "MNT_1_4") (pintype "passive+no_connect"))
    )
    (net (code "44") (name "unconnected-(J2-MNT_2-Pad5)") (class "Default")
      (node (ref "J2") (pin "5") (pinfunction "MNT_2_5") (pintype "passive+no_connect"))
    )
    (net (code "45") (name "unconnected-(J3-MNT_1-Pad4)") (class "Default")
      (node (ref "J3") (pin "4") (pinfunction "MNT_1_4") (pintype "passive+no_connect"))
    )
    (net (code "46") (name "unconnected-(J3-MNT_2-Pad5)") (class "Default")
      (node (ref "J3") (pin "5") (pinfunction "MNT_2_5") (pintype "passive+no_connect"))
    )
    (net (code "47") (name "unconnected-(J3-Pad2)") (class "Default")
      (node (ref "J3") (pin "2") (pinfunction "2_2") (pintype "passive+no_connect"))
    )
    (net (code "48") (name "unconnected-(P2-Pad6)") (class "Default")
      (node (ref "P2") (pin "6") (pintype "passive+no_connect"))
    )
    (net (code "49") (name "unconnected-(P3-PadMP1)") (class "Default")
      (node (ref "P3") (pin "MP1") (pinfunction "MP1_MP1") (pintype "passive+no_connect"))
    )
    (net (code "50") (name "unconnected-(P3-PadMP2)") (class "Default")
      (node (ref "P3") (pin "MP2") (pinfunction "MP2_MP2") (pintype "passive+no_connect"))
    )
    (net (code "51") (name "unconnected-(U1-LDO18_O-Pad8)") (class "Default")
      (node (ref "U1") (pin "8") (pinfunction "LDO18_O_8") (pintype "output+no_connect"))
    )
    (net (code "52") (name "unconnected-(U1-P0_5-Pad16)") (class "Default")
      (node (ref "U1") (pin "16") (pinfunction "P0_5_16") (pintype "bidirectional+no_connect"))
    )
    (net (code "53") (name "unconnected-(U1-P1_2-Pad13)") (class "Default")
      (node (ref "U1") (pin "13") (pinfunction "P1_2_13") (pintype "output+no_connect"))
    )
    (net (code "54") (name "unconnected-(U1-P1_3-Pad14)") (class "Default")
      (node (ref "U1") (pin "14") (pinfunction "P1_3_14") (pintype "bidirectional+no_connect"))
    )
    (net (code "55") (name "unconnected-(U1-P3_1-Pad24)") (class "Default")
      (node (ref "U1") (pin "24") (pinfunction "P3_1_24") (pintype "bidirectional+no_connect"))
    )
    (net (code "56") (name "unconnected-(U1-P3_2-Pad25)") (class "Default")
      (node (ref "U1") (pin "25") (pinfunction "P3_2_25") (pintype "bidirectional+no_connect"))
    )
    (net (code "57") (name "unconnected-(U1-P3_3-Pad26)") (class "Default")
      (node (ref "U1") (pin "26") (pinfunction "P3_3_26") (pintype "bidirectional+no_connect"))
    )
    (net (code "58") (name "unconnected-(U1-P3_4-Pad27)") (class "Default")
      (node (ref "U1") (pin "27") (pinfunction "P3_4_27") (pintype "bidirectional+no_connect"))
    )
    (net (code "59") (name "unconnected-(U1-P3_6-Pad28)") (class "Default")
      (node (ref "U1") (pin "28") (pinfunction "P3_6_28") (pintype "bidirectional+no_connect"))
    )
    (net (code "60") (name "unconnected-(U1-P3_7-Pad29)") (class "Default")
      (node (ref "U1") (pin "29") (pinfunction "P3_7_29") (pintype "bidirectional+no_connect"))
    )
    (net (code "61") (name "unconnected-(U1-PMULDO_O-Pad10)") (class "Default")
      (node (ref "U1") (pin "10") (pinfunction "PMULDO_O_10") (pintype "output+no_connect"))
    )
    (net (code "62") (name "unconnected-(U1-WAKEUP-Pad9)") (class "Default")
      (node (ref "U1") (pin "9") (pinfunction "WAKEUP_9") (pintype "input+no_connect"))
    )
    (net (code "63") (name "unconnected-(U3-NC-Pad4)") (class "Default")
      (node (ref "U3") (pin "4") (pinfunction "NC_4") (pintype "passive+no_connect"))
    )
    (net (code "64") (name "unconnected-(U4-INT1{slash}INT-Pad4)") (class "Default")
      (node (ref "U4") (pin "4") (pinfunction "INT1/INT_4") (pintype "output+no_connect"))
    )
    (net (code "65") (name "unconnected-(U4-INT2-Pad9)") (class "Default")
      (node (ref "U4") (pin "9") (pinfunction "INT2_9") (pintype "output+no_connect"))
    )
    (net (code "66") (name "unconnected-(U4-RESV_2-Pad2)") (class "Default")
      (node (ref "U4") (pin "2") (pinfunction "RESV_2_2") (pintype "passive+no_connect"))
    )
    (net (code "67") (name "unconnected-(U4-RESV_3-Pad3)") (class "Default")
      (node (ref "U4") (pin "3") (pinfunction "RESV_3_3") (pintype "passive+no_connect"))
    )
    (net (code "68") (name "unconnected-(U4-RESV_10-Pad10)") (class "Default")
      (node (ref "U4") (pin "10") (pinfunction "RESV_10_10") (pintype "passive+no_connect"))
    )
    (net (code "69") (name "unconnected-(U4-RESV_11-Pad11)") (class "Default")
      (node (ref "U4") (pin "11") (pinfunction "RESV_11_11") (pintype "passive+no_connect"))
    )
    (net (code "70") (name "unconnected-(U5-OSC2{slash}CLKO{slash}RPA3{slash}PMA0{slash}RA3-Pad10)") (class "Default")
      (node (ref "U5") (pin "10") (pinfunction "OSC2/CLKO/RPA3/PMA0/RA3_10") (pintype "bidirectional+no_connect"))
    )
    (net (code "71") (name "unconnected-(U5-PGED3{slash}RPB5{slash}PMD7{slash}RB5-Pad14)") (class "Default")
      (node (ref "U5") (pin "14") (pinfunction "PGED3/RPB5/PMD7/RB5_14") (pintype "output+no_connect"))
    )
    (net (code "72") (name "unconnected-(U5-SOSCI{slash}RPB4{slash}RB4-Pad11)") (class "Default")
      (node (ref "U5") (pin "11") (pinfunction "SOSCI/RPB4/RB4_11") (pintype "bidirectional+no_connect"))
    )
    (net (code "73") (name "unconnected-(U5-SOSCO{slash}RPA4{slash}T1CK{slash}CTED9{slash}PMA1{slash}RA4-Pad12)") (class "Default")
      (node (ref "U5") (pin "12") (pinfunction "SOSCO/RPA4/T1CK/CTED9/PMA1/RA4_12") (pintype "bidirectional+no_connect"))
    )
    (net (code "74") (name "unconnected-(U5-VREF+{slash}CVREF+{slash}AN0{slash}C3INC{slash}RPA0{slash}CTED1{slash}RA0-Pad2)") (class "Default")
      (node (ref "U5") (pin "2") (pinfunction "VREF+/CVREF+/AN0/C3INC/RPA0/CTED1/RA0_2") (pintype "bidirectional+no_connect"))
    )
    (net (code "75") (name "unconnected-(U6-NC-Pad5)") (class "Default")
      (node (ref "U6") (pin "5") (pinfunction "NC_5") (pintype "passive+no_connect"))
    )
    (net (code "76") (name "unconnected-(U6-NC-Pad6)") (class "Default")
      (node (ref "U6") (pin "6") (pinfunction "NC_6") (pintype "passive+no_connect"))
    )
    (net (code "77") (name "unconnected-(U6-NC-Pad7)") (class "Default")
      (node (ref "U6") (pin "7") (pinfunction "NC_7") (pintype "passive+no_connect"))
    )
    (net (code "78") (name "unconnected-(U6-NC-Pad8)") (class "Default")
      (node (ref "U6") (pin "8") (pinfunction "NC_8") (pintype "passive+no_connect"))
    )
  )
)
